# WeMos-ILI9341-Shield.net
KiCad netlist of a schematic drawn in EAGLE
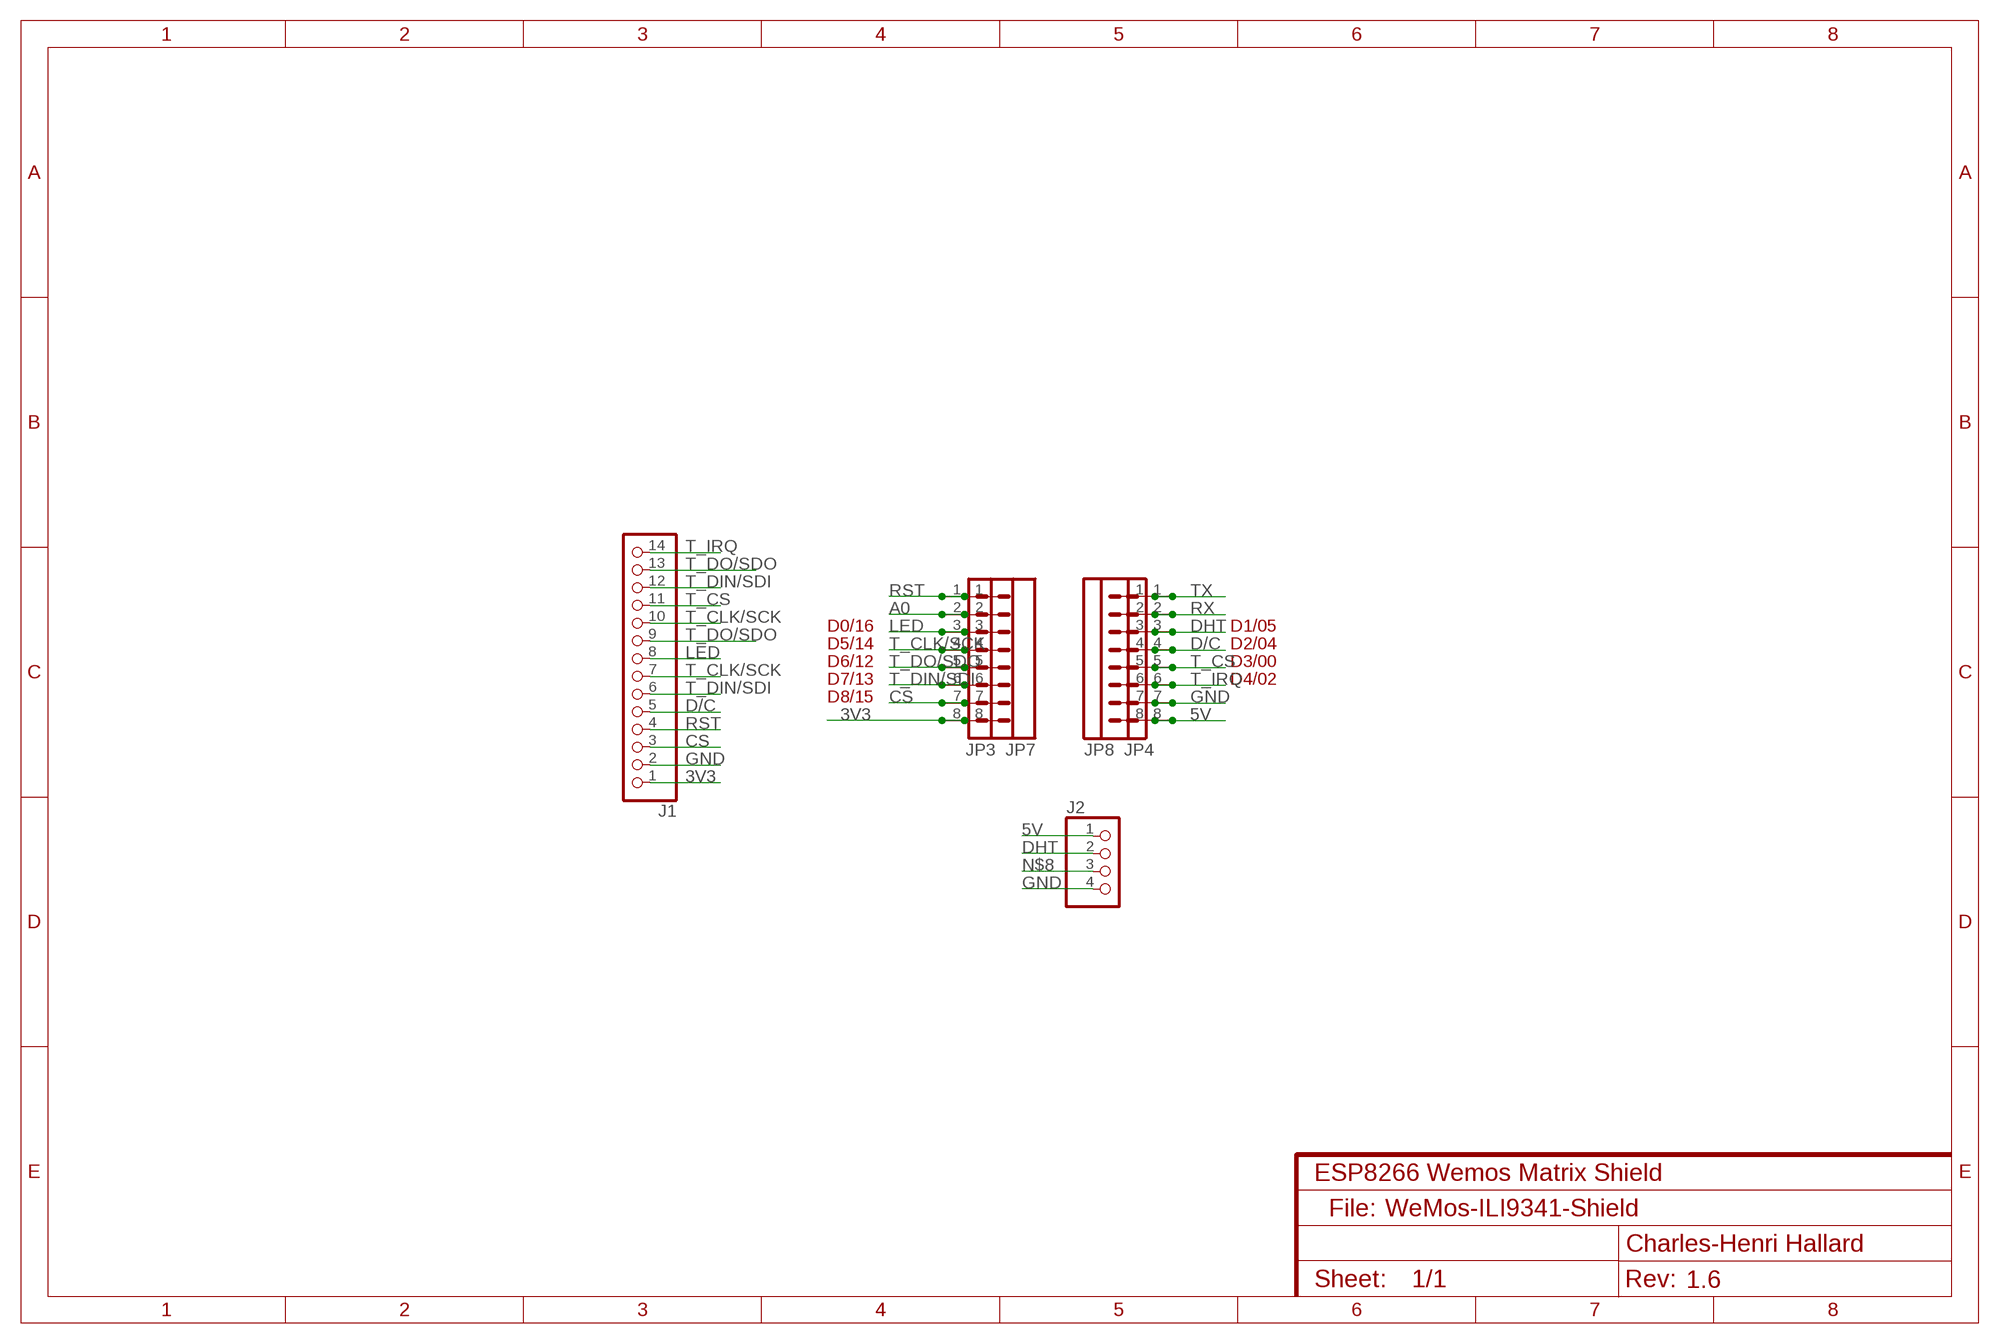
[diagram p0: schematic, sheet 1]

(export (version "E")
  (design (tool "Eeschema 10.0.6"))
  (components
    (comp (ref "J1")
      (value "PINHD-1X14")
      (footprint "eagle-import:1X14")
      (libsource (lib "eagle-import") (part "PINHD-1X14"))
    )
    (comp (ref "J2")
      (value "HEADER-1X4")
      (footprint "eagle-import:1X04_OVAL")
      (libsource (lib "eagle-import") (part "HEADER-1X4"))
    )
    (comp (ref "JP3")
      (value "M08NO_SILK_FEMALE_PTH")
      (footprint "eagle-import:1X08_NO_SILK")
      (libsource (lib "eagle-import") (part "M08NO_SILK_FEMALE_PTH"))
    )
    (comp (ref "JP4")
      (value "M08NO_SILK_FEMALE_PTH")
      (footprint "eagle-import:1X08_NO_SILK")
      (libsource (lib "eagle-import") (part "M08NO_SILK_FEMALE_PTH"))
    )
    (comp (ref "JP7")
      (value "M08NO_SILK_FEMALE_PTH")
      (footprint "eagle-import:1X08_NO_SILK")
      (libsource (lib "eagle-import") (part "M08NO_SILK_FEMALE_PTH"))
    )
    (comp (ref "JP8")
      (value "M08NO_SILK_FEMALE_PTH")
      (footprint "eagle-import:1X08_NO_SILK")
      (libsource (lib "eagle-import") (part "M08NO_SILK_FEMALE_PTH"))
    )
  )
  (nets
    (net (code "1") (name "/3V3") (class "Default")
      (node (ref "J1") (pin "1") (pinfunction "1_1") (pintype "passive"))
      (node (ref "JP3") (pin "8") (pinfunction "8_8") (pintype "passive"))
      (node (ref "JP7") (pin "8") (pinfunction "8_8") (pintype "passive"))
    )
    (net (code "2") (name "/5V") (class "Default")
      (node (ref "J2") (pin "1") (pinfunction "1_1") (pintype "passive"))
      (node (ref "JP4") (pin "8") (pinfunction "8_8") (pintype "passive"))
      (node (ref "JP8") (pin "8") (pinfunction "8_8") (pintype "passive"))
    )
    (net (code "3") (name "/A0") (class "Default")
      (node (ref "JP3") (pin "2") (pinfunction "2_2") (pintype "passive"))
      (node (ref "JP7") (pin "2") (pinfunction "2_2") (pintype "passive"))
    )
    (net (code "4") (name "/CS") (class "Default")
      (node (ref "J1") (pin "3") (pinfunction "3_3") (pintype "passive"))
      (node (ref "JP3") (pin "7") (pinfunction "7_7") (pintype "passive"))
      (node (ref "JP7") (pin "7") (pinfunction "7_7") (pintype "passive"))
    )
    (net (code "5") (name "/DHT") (class "Default")
      (node (ref "J2") (pin "2") (pinfunction "2_2") (pintype "passive"))
      (node (ref "JP4") (pin "3") (pinfunction "3_3") (pintype "passive"))
      (node (ref "JP8") (pin "3") (pinfunction "3_3") (pintype "passive"))
    )
    (net (code "6") (name "/D{slash}C") (class "Default")
      (node (ref "J1") (pin "5") (pinfunction "5_5") (pintype "passive"))
      (node (ref "JP4") (pin "4") (pinfunction "4_4") (pintype "passive"))
      (node (ref "JP8") (pin "4") (pinfunction "4_4") (pintype "passive"))
    )
    (net (code "7") (name "/GND") (class "Default")
      (node (ref "J1") (pin "2") (pinfunction "2_2") (pintype "passive"))
      (node (ref "J2") (pin "4") (pinfunction "4_4") (pintype "passive"))
      (node (ref "JP4") (pin "7") (pinfunction "7_7") (pintype "passive"))
      (node (ref "JP8") (pin "7") (pinfunction "7_7") (pintype "passive"))
    )
    (net (code "8") (name "/LED") (class "Default")
      (node (ref "J1") (pin "8") (pinfunction "8_8") (pintype "passive"))
      (node (ref "JP3") (pin "3") (pinfunction "3_3") (pintype "passive"))
      (node (ref "JP7") (pin "3") (pinfunction "3_3") (pintype "passive"))
    )
    (net (code "9") (name "/N$8") (class "Default")
      (node (ref "J2") (pin "3") (pinfunction "3_3") (pintype "passive"))
    )
    (net (code "10") (name "/RST") (class "Default")
      (node (ref "J1") (pin "4") (pinfunction "4_4") (pintype "passive"))
      (node (ref "JP3") (pin "1") (pinfunction "1_1") (pintype "passive"))
      (node (ref "JP7") (pin "1") (pinfunction "1_1") (pintype "passive"))
    )
    (net (code "11") (name "/RX") (class "Default")
      (node (ref "JP4") (pin "2") (pinfunction "2_2") (pintype "passive"))
      (node (ref "JP8") (pin "2") (pinfunction "2_2") (pintype "passive"))
    )
    (net (code "12") (name "/TX") (class "Default")
      (node (ref "JP4") (pin "1") (pinfunction "1_1") (pintype "passive"))
      (node (ref "JP8") (pin "1") (pinfunction "1_1") (pintype "passive"))
    )
    (net (code "13") (name "/T_CLK{slash}SCK") (class "Default")
      (node (ref "J1") (pin "10") (pinfunction "10_10") (pintype "passive"))
      (node (ref "J1") (pin "7") (pinfunction "7_7") (pintype "passive"))
      (node (ref "JP3") (pin "4") (pinfunction "4_4") (pintype "passive"))
      (node (ref "JP7") (pin "4") (pinfunction "4_4") (pintype "passive"))
    )
    (net (code "14") (name "/T_CS") (class "Default")
      (node (ref "J1") (pin "11") (pinfunction "11_11") (pintype "passive"))
      (node (ref "JP4") (pin "5") (pinfunction "5_5") (pintype "passive"))
      (node (ref "JP8") (pin "5") (pinfunction "5_5") (pintype "passive"))
    )
    (net (code "15") (name "/T_DIN{slash}SDI") (class "Default")
      (node (ref "J1") (pin "12") (pinfunction "12_12") (pintype "passive"))
      (node (ref "J1") (pin "6") (pinfunction "6_6") (pintype "passive"))
      (node (ref "JP3") (pin "6") (pinfunction "6_6") (pintype "passive"))
      (node (ref "JP7") (pin "6") (pinfunction "6_6") (pintype "passive"))
    )
    (net (code "16") (name "/T_DO{slash}SDO") (class "Default")
      (node (ref "J1") (pin "13") (pinfunction "13_13") (pintype "passive"))
      (node (ref "J1") (pin "9") (pinfunction "9_9") (pintype "passive"))
      (node (ref "JP3") (pin "5") (pinfunction "5_5") (pintype "passive"))
      (node (ref "JP7") (pin "5") (pinfunction "5_5") (pintype "passive"))
    )
    (net (code "17") (name "/T_IRQ") (class "Default")
      (node (ref "J1") (pin "14") (pinfunction "14_14") (pintype "passive"))
      (node (ref "JP4") (pin "6") (pinfunction "6_6") (pintype "passive"))
      (node (ref "JP8") (pin "6") (pinfunction "6_6") (pintype "passive"))
    )
  )
)
